# BMS_Schematic.net
KiCad netlist of a schematic drawn in Altium Designer
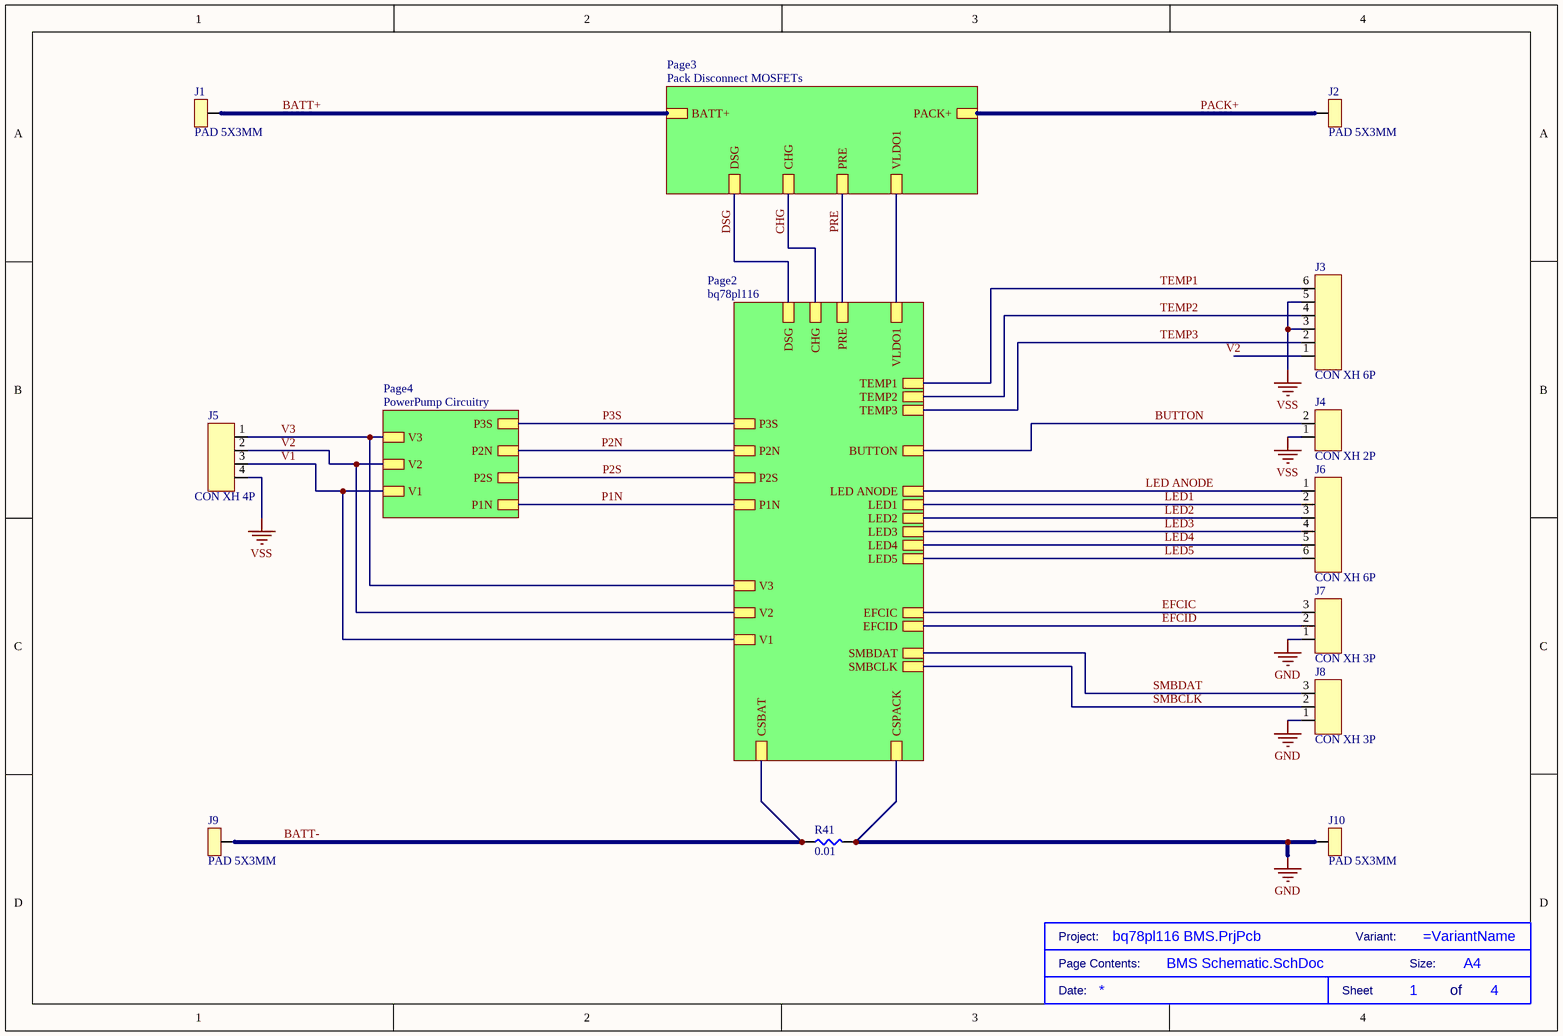
[diagram p0: BMS Schematic.SchDoc]

(export (version "E")
  (design (tool "Eeschema 10.0.6"))
  (components
    (comp (ref "J1") (value "PAD 5X3MM") (footprint "PAD 5X3MM") (libsource (lib "") (part "PAD 5X3MM_1")))
    (comp (ref "J2")
      (value "PAD 5X3MM")
      (footprint "PAD 5X3MM")
      (libsource (lib "MyLibrary") (part "PAD 5X3MM"))
    )
    (comp (ref "J3")
      (value "CON XH 6P")
      (footprint "XH 2.5 6P")
      (description "CONN HEADER VERT 6POS 2.5MM")
      (fields (field (name "MANUFACTURER") "JST") (field (name "MANUFACTURER PART NUMBER") "B6BXHA(LF)(SN)"))
      (libsource (lib "") (part "CONN XH 2.5 6P_1"))
    )
    (comp (ref "J4")
      (value "CON XH 2P")
      (footprint "XH 2.5 2P")
      (description "2 Position Dual Row 2.5 mm Pitch Through Hole Shrouded Header")
      (fields (field (name "MANUFACTURER") "JST") (field (name "MANUFACTURER PART NUMBER") "B2B-XH-A-GU"))
      (libsource (lib "MyLibrary") (part "CONN XH 2.5 2P"))
    )
    (comp (ref "J5")
      (value "CON XH 4P")
      (footprint "XH 2.5 4P")
      (description "XH Series 4 Position 2.5 mm Pitch Through Hole Crimp Top Entry Shrouded Header")
      (fields
        (field (name "MANUFACTURER") "JST")
        (field (name "MANUFACTURER PART NUMBER") "B4B-XH-A(LF)(SN)")
      )
      (libsource (lib "MyLibrary") (part "CONN XH 2.5 4P"))
    )
    (comp (ref "J6")
      (value "CON XH 6P")
      (footprint "XH 2.5 6P")
      (description "CONN HEADER VERT 6POS 2.5MM")
      (fields (field (name "MANUFACTURER") "JST") (field (name "MANUFACTURER PART NUMBER") "B6BXHA(LF)(SN)"))
      (libsource (lib "MyLibrary") (part "CONN XH 2.5 6P"))
    )
    (comp (ref "J7")
      (value "CON XH 3P")
      (footprint "XH 2.5 3P")
      (description "Connector Header, XH Series, 3 Position, 2.50mm, Through Hole, Press-Fit, Solder, Natural")
      (fields
        (field (name "MANUFACTURER") "JST")
        (field (name "MANUFACTURER PART NUMBER") "B3B-XH-A(LF)(SN)")
      )
      (libsource (lib "MyLibrary") (part "CONN XH 2.5 3P"))
    )
    (comp (ref "J8")
      (value "CON XH 3P")
      (footprint "XH 2.5 3P")
      (description "Connector Header, XH Series, 3 Position, 2.50mm, Through Hole, Press-Fit, Solder, Natural")
      (fields
        (field (name "MANUFACTURER") "JST")
        (field (name "MANUFACTURER PART NUMBER") "B3B-XH-A(LF)(SN)")
      )
      (libsource (lib "MyLibrary") (part "CONN XH 2.5 3P"))
    )
    (comp (ref "J9") (value "PAD 5X3MM") (footprint "PAD 5X3MM") (libsource (lib "") (part "PAD 5X3MM_1")))
    (comp (ref "J10")
      (value "PAD 5X3MM")
      (footprint "PAD 5X3MM")
      (libsource (lib "MyLibrary") (part "PAD 5X3MM"))
    )
    (comp (ref "R41") (value "0.01") (footprint "RSHUNT") (libsource (lib "MyLibrary") (part "SHUNT 10m")))
  )
  (nets
    (net (code "1") (name "/BATT+") (class "Default")
      (node (ref "J1") (pin "1") (pinfunction "1_1") (pintype "passive"))
    )
    (net (code "2") (name "/BATT-") (class "Default")
      (node (ref "J9") (pin "1") (pinfunction "1_1") (pintype "passive"))
      (node (ref "R41") (pin "1") (pinfunction "1_1") (pintype "passive"))
    )
    (net (code "3") (name "/BUTTON") (class "Default")
      (node (ref "J4") (pin "2") (pinfunction "2_2") (pintype "passive"))
    )
    (net (code "6") (name "/EFCIC") (class "Default")
      (node (ref "J7") (pin "3") (pinfunction "3_3") (pintype "passive"))
    )
    (net (code "7") (name "/EFCID") (class "Default")
      (node (ref "J7") (pin "2") (pinfunction "2_2") (pintype "passive"))
    )
    (net (code "8") (name "/LED ANODE") (class "Default")
      (node (ref "J6") (pin "1") (pinfunction "1_1") (pintype "passive"))
    )
    (net (code "9") (name "/LED1") (class "Default")
      (node (ref "J6") (pin "2") (pinfunction "2_2") (pintype "passive"))
    )
    (net (code "10") (name "/LED2") (class "Default")
      (node (ref "J6") (pin "3") (pinfunction "3_3") (pintype "passive"))
    )
    (net (code "11") (name "/LED3") (class "Default")
      (node (ref "J6") (pin "4") (pinfunction "4_4") (pintype "passive"))
    )
    (net (code "12") (name "/LED4") (class "Default")
      (node (ref "J6") (pin "5") (pinfunction "5_5") (pintype "passive"))
    )
    (net (code "13") (name "/LED5") (class "Default")
      (node (ref "J6") (pin "6") (pinfunction "6_6") (pintype "passive"))
    )
    (net (code "18") (name "/PACK+") (class "Default")
      (node (ref "J2") (pin "1") (pinfunction "1_1") (pintype "passive"))
    )
    (net (code "20") (name "/SMBCLK") (class "Default")
      (node (ref "J8") (pin "2") (pinfunction "2_2") (pintype "passive"))
    )
    (net (code "21") (name "/SMBDAT") (class "Default")
      (node (ref "J8") (pin "3") (pinfunction "3_3") (pintype "passive"))
    )
    (net (code "22") (name "/TEMP1") (class "Default")
      (node (ref "J3") (pin "6") (pinfunction "6_6") (pintype "passive"))
    )
    (net (code "23") (name "/TEMP2") (class "Default")
      (node (ref "J3") (pin "4") (pinfunction "4_4") (pintype "passive"))
    )
    (net (code "24") (name "/TEMP3") (class "Default")
      (node (ref "J3") (pin "2") (pinfunction "2_2") (pintype "passive"))
    )
    (net (code "25") (name "/V1") (class "Default")
      (node (ref "J5") (pin "3") (pinfunction "3_3") (pintype "passive"))
    )
    (net (code "26") (name "/V2") (class "Default")
      (node (ref "J3") (pin "1") (pinfunction "1_1") (pintype "passive"))
      (node (ref "J5") (pin "2") (pinfunction "2_2") (pintype "passive"))
    )
    (net (code "27") (name "/V3") (class "Default")
      (node (ref "J5") (pin "1") (pinfunction "1_1") (pintype "passive"))
    )
    (net (code "29") (name "GND") (class "Default")
      (node (ref "J10") (pin "1") (pinfunction "1_1") (pintype "passive"))
      (node (ref "J7") (pin "1") (pinfunction "1_1") (pintype "passive"))
      (node (ref "J8") (pin "1") (pinfunction "1_1") (pintype "passive"))
      (node (ref "R41") (pin "2") (pinfunction "2_2") (pintype "passive"))
    )
    (net (code "30") (name "VSS") (class "Default")
      (node (ref "J3") (pin "3") (pinfunction "3_3") (pintype "passive"))
      (node (ref "J3") (pin "5") (pinfunction "5_5") (pintype "passive"))
      (node (ref "J4") (pin "1") (pinfunction "1_1") (pintype "passive"))
      (node (ref "J5") (pin "4") (pinfunction "4_4") (pintype "passive"))
    )
  )
)
